# Sensor.net
KiCad netlist of a schematic drawn in Altium Designer
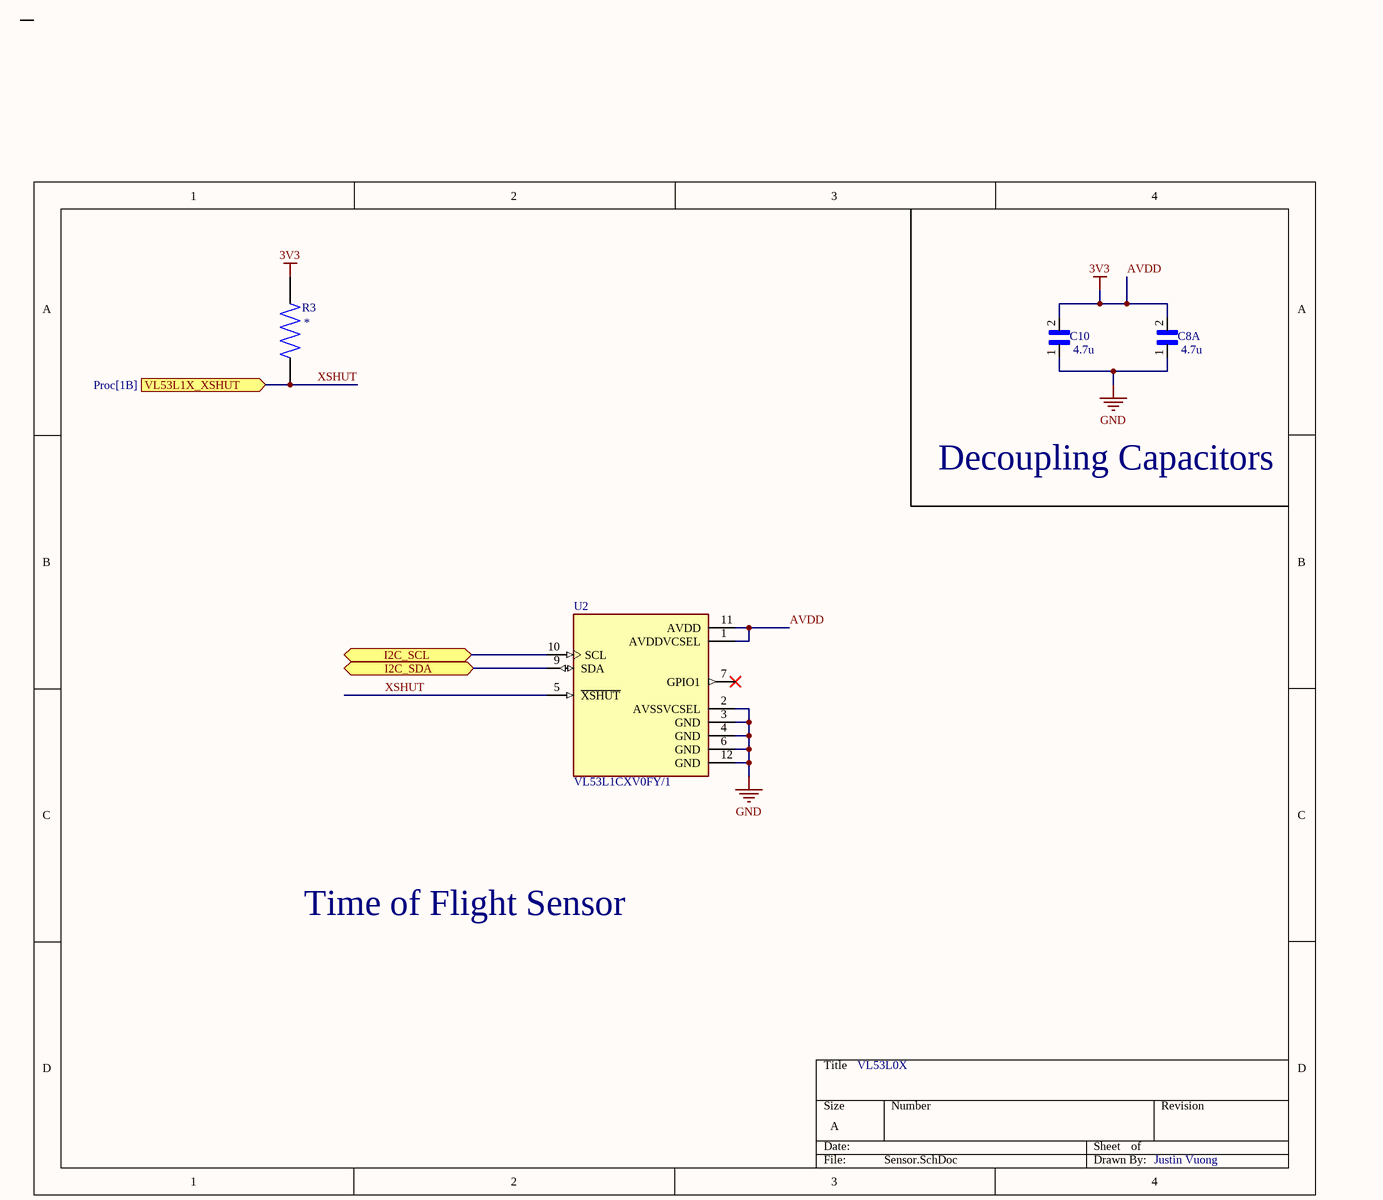
[diagram p0: Sensor.SchDoc]

(export (version "E")
  (design (tool "Eeschema 10.0.6"))
  (components
    (comp (ref "C8")
      (value "4.7u")
      (footprint "CAPC0603X33N")
      (description "4.7 µF ±10% 6.3V Ceramic Capacitor X5R 0603 (1608 Metric)")
      (fields (field (name "MF") "Murata") (field (name "MP") "GRM0335C1H1R6BA01D"))
      (libsource (lib "CL10A475KQ8NNNC") (part "GRM0335C1H1R6BA01D"))
    )
    (comp (ref "C10")
      (value "4.7u")
      (footprint "04025A8R2CAT2A:CAPC1005X56N")
      (description "4.7 µF ±10% 6.3V Ceramic Capacitor X5R 0603 (1608 Metric)")
      (fields (field (name "DIGI-KEY_PART_NUMBER") "478-1069-1-ND") (field (name "MF") "AVX"))
      (libsource (lib "CL05B104KA5NNNC") (part "04025A8R2CAT2A"))
    )
    (comp (ref "R3")
      (value "AC0402FR-0710KL")
      (footprint "RESC1005X37N")
      (fields
        (field (name "ALTIUM_VALUE") "*")
        (field (name "DIGI-KEY_PART_NUMBER") "YAG3436TR-ND")
        (field (name "MF") "Yageo")
      )
      (libsource (lib "AC0402FR-0710KL") (part "AC0402FR-0710KL"))
    )
    (comp (ref "U2")
      (value "VL53L1CXV0FY/1")
      (footprint "SENSOR_VL53L1CXV0FY/1")
      (description "Optical Sensor 157.480 (4m) IÂ²C Output")
      (fields (field (name "MF") "STMicroelectronics"))
      (libsource (lib "VL53L1CXV0FY_1") (part "VL53L1CXV0FY/1"))
    )
  )
  (nets
    (net (code "1") (name "/I2C_SCL") (class "Default")
      (node (ref "U2") (pin "10") (pinfunction "SCL_10") (pintype "input"))
    )
    (net (code "2") (name "/I2C_SDA") (class "Default")
      (node (ref "U2") (pin "9") (pinfunction "SDA_9") (pintype "bidirectional"))
    )
    (net (code "3") (name "/XSHUT") (class "Default")
      (node (ref "R3") (pin "1") (pinfunction "1_1") (pintype "passive"))
      (node (ref "U2") (pin "5") (pinfunction "~{XSHUT}_5") (pintype "input"))
    )
    (net (code "4") (name "3V3") (class "Default")
      (node (ref "C10") (pin "2") (pinfunction "2_2") (pintype "passive"))
      (node (ref "C8") (pin "2") (pinfunction "2_2") (pintype "passive"))
      (node (ref "R3") (pin "2") (pinfunction "2_2") (pintype "passive"))
      (node (ref "U2") (pin "1") (pinfunction "AVDDVCSEL_1") (pintype "power_in"))
      (node (ref "U2") (pin "11") (pinfunction "AVDD_11") (pintype "power_in"))
    )
    (net (code "5") (name "GND") (class "Default")
      (node (ref "C10") (pin "1") (pinfunction "1_1") (pintype "passive"))
      (node (ref "C8") (pin "1") (pinfunction "1_1") (pintype "passive"))
      (node (ref "U2") (pin "12") (pinfunction "GND_12") (pintype "power_in"))
      (node (ref "U2") (pin "2") (pinfunction "AVSSVCSEL_2") (pintype "power_in"))
      (node (ref "U2") (pin "3") (pinfunction "GND_3") (pintype "power_in"))
      (node (ref "U2") (pin "4") (pinfunction "GND_4") (pintype "power_in"))
      (node (ref "U2") (pin "6") (pinfunction "GND_6") (pintype "power_in"))
    )
    (net (code "6") (name "unconnected-(U2-GPIO1-Pad7)") (class "Default")
      (node (ref "U2") (pin "7") (pinfunction "GPIO1_7") (pintype "output+no_connect"))
    )
  )
)
